# contactor_control.net
KiCad netlist of a schematic drawn in Altium Designer
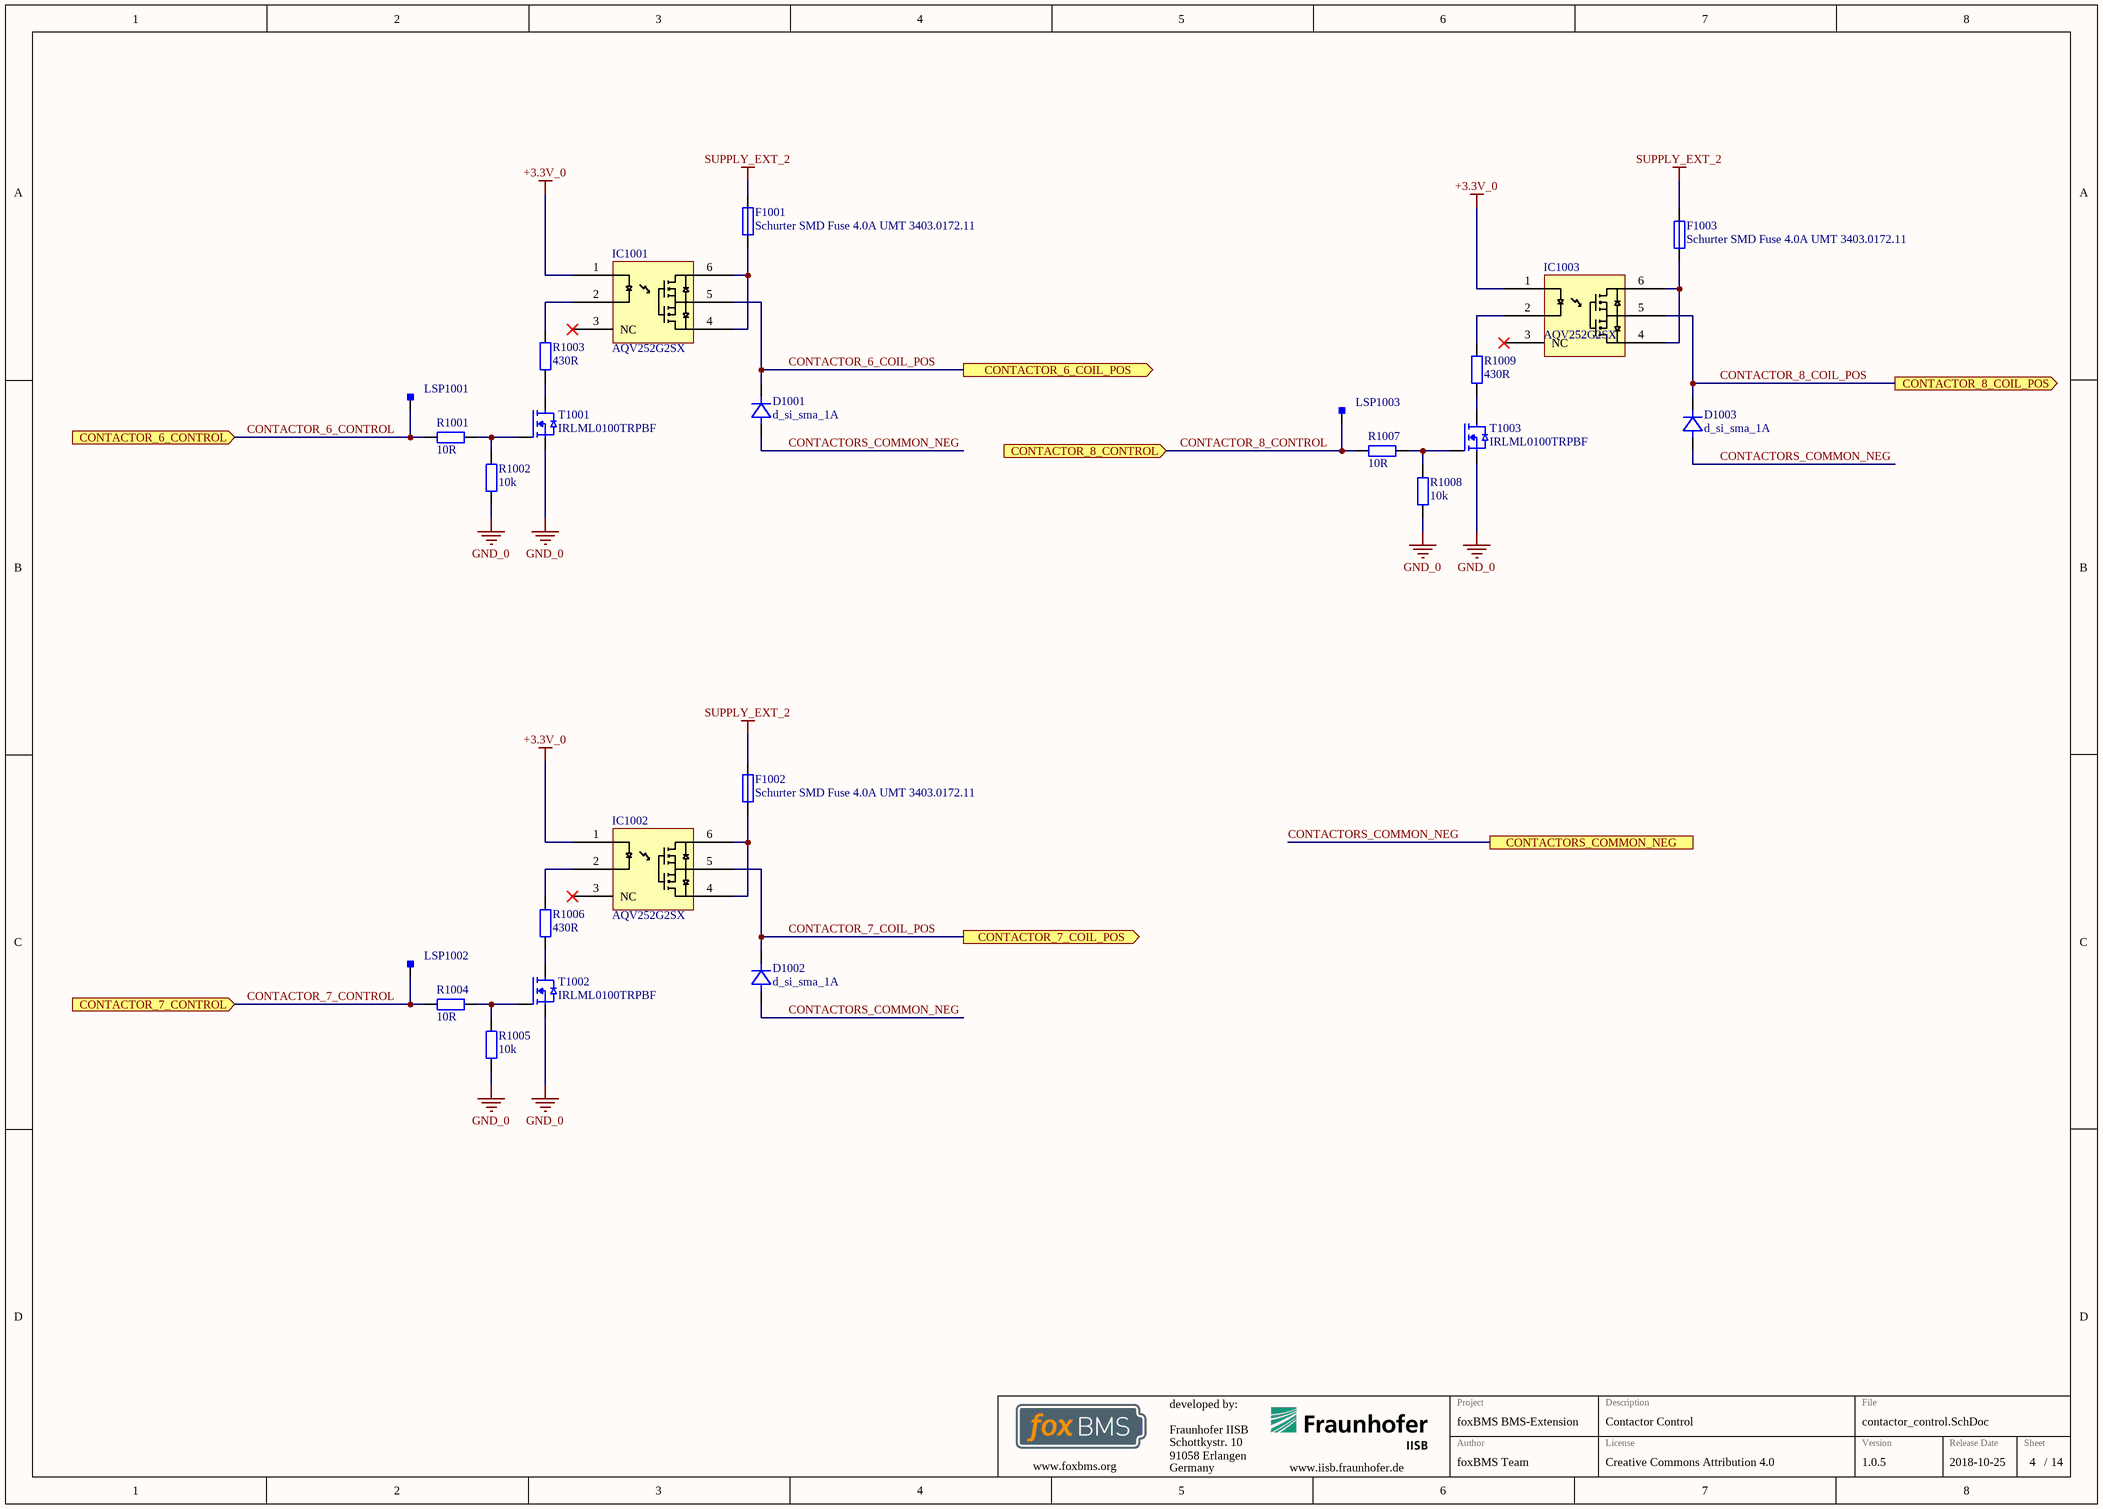
[diagram p0: contactor_control.SchDoc]

(export (version "E")
  (design (tool "Eeschema 10.0.6"))
  (components
    (comp (ref "D1001")
      (value "d_si_sma_1A")
      (footprint "DIOM4326X24N")
      (description "Standard Recovery Diode, 100 V, 1 A, Single, 1 V, 2 µs, 30 A")
      (fields (field (name "MANUFACTURER") "ON Semiconductor"))
      (libsource (lib "OE750") (part "D"))
    )
    (comp (ref "D1002")
      (value "d_si_sma_1A")
      (footprint "DIOM4326X24N")
      (description "Standard Recovery Diode, 100 V, 1 A, Single, 1 V, 2 µs, 30 A")
      (fields (field (name "MANUFACTURER") "ON Semiconductor"))
      (libsource (lib "OE750") (part "D"))
    )
    (comp (ref "D1003")
      (value "d_si_sma_1A")
      (footprint "DIOM4326X24N")
      (description "Standard Recovery Diode, 100 V, 1 A, Single, 1 V, 2 µs, 30 A")
      (fields (field (name "MANUFACTURER") "ON Semiconductor"))
      (libsource (lib "OE750") (part "D"))
    )
    (comp (ref "F1001")
      (value "Schurter SMD Fuse 4.0A UMT 3403.0172.11")
      (footprint "Schurter_UMT_250")
      (fields (field (name "PART NUMBER") "fuse_4A_3403.0172.11") (field (name "MANUFACTURER") "Schurter"))
      (libsource (lib "OE750") (part "R_Fuse"))
    )
    (comp (ref "F1002")
      (value "Schurter SMD Fuse 4.0A UMT 3403.0172.11")
      (footprint "Schurter_UMT_250")
      (fields (field (name "PART NUMBER") "fuse_4A_3403.0172.11") (field (name "MANUFACTURER") "Schurter"))
      (libsource (lib "OE750") (part "R_Fuse"))
    )
    (comp (ref "F1003")
      (value "Schurter SMD Fuse 4.0A UMT 3403.0172.11")
      (footprint "Schurter_UMT_250")
      (fields (field (name "PART NUMBER") "fuse_4A_3403.0172.11") (field (name "MANUFACTURER") "Schurter"))
      (libsource (lib "OE750") (part "R_Fuse"))
    )
    (comp (ref "IC1001")
      (value "AQV252G2SX")
      (footprint "SOP254P680X220-6N")
      (description "PhotoMOS Relay")
      (fields (field (name "MANUFACTURER") "Panasonic"))
      (libsource (lib "OE750") (part "AQV252G2SX"))
    )
    (comp (ref "IC1002")
      (value "AQV252G2SX")
      (footprint "SOP254P680X220-6N")
      (description "PhotoMOS Relay")
      (fields (field (name "MANUFACTURER") "Panasonic"))
      (libsource (lib "OE750") (part "AQV252G2SX"))
    )
    (comp (ref "IC1003")
      (value "AQV252G2SX")
      (footprint "SOP254P680X220-6N")
      (description "PhotoMOS Relay")
      (fields (field (name "MANUFACTURER") "Panasonic"))
      (libsource (lib "OE750") (part "AQV252G2SX"))
    )
    (comp (ref "LSP1001")
      (value "Testpoint_Square")
      (footprint "Testpoint_S1")
      (description "Testpoint, square")
      (libsource (lib "OE750") (part "Testpoint_Square"))
    )
    (comp (ref "LSP1002")
      (value "Testpoint_Square")
      (footprint "Testpoint_S1")
      (description "Testpoint, square")
      (libsource (lib "OE750") (part "Testpoint_Square"))
    )
    (comp (ref "LSP1003")
      (value "Testpoint_Square")
      (footprint "Testpoint_S1")
      (description "Testpoint, square")
      (libsource (lib "OE750") (part "Testpoint_Square"))
    )
    (comp (ref "R1001")
      (value "10R")
      (footprint "RESC1608X05N")
      (description "SMD Resistor 10R 0603")
      (fields (field (name "PART NUMBER") "gen_R_10R_0603") (field (name "TOLERANCE") "1%"))
      (libsource (lib "OE750") (part "R"))
    )
    (comp (ref "R1002")
      (value "10k")
      (footprint "RESC1608X05N")
      (description "SMD Resistor 10k 0603")
      (fields (field (name "PART NUMBER") "gen_R_10k_0603") (field (name "TOLERANCE") "1%"))
      (libsource (lib "OE750") (part "R"))
    )
    (comp (ref "R1003")
      (value "430R")
      (footprint "RESC1608X05N")
      (description "SMD Resistor 430R 0603")
      (fields (field (name "PART NUMBER") "gen_R_430R_0603") (field (name "TOLERANCE") "1%"))
      (libsource (lib "OE750") (part "R"))
    )
    (comp (ref "R1004")
      (value "10R")
      (footprint "RESC1608X05N")
      (description "SMD Resistor 10R 0603")
      (fields (field (name "PART NUMBER") "gen_R_10R_0603") (field (name "TOLERANCE") "1%"))
      (libsource (lib "OE750") (part "R"))
    )
    (comp (ref "R1005")
      (value "10k")
      (footprint "RESC1608X05N")
      (description "SMD Resistor 10k 0603")
      (fields (field (name "PART NUMBER") "gen_R_10k_0603") (field (name "TOLERANCE") "1%"))
      (libsource (lib "OE750") (part "R"))
    )
    (comp (ref "R1006")
      (value "430R")
      (footprint "RESC1608X05N")
      (description "SMD Resistor 430R 0603")
      (fields (field (name "PART NUMBER") "gen_R_430R_0603") (field (name "TOLERANCE") "1%"))
      (libsource (lib "OE750") (part "R"))
    )
    (comp (ref "R1007")
      (value "10R")
      (footprint "RESC1608X05N")
      (description "SMD Resistor 10R 0603")
      (fields (field (name "PART NUMBER") "gen_R_10R_0603") (field (name "TOLERANCE") "1%"))
      (libsource (lib "OE750") (part "R"))
    )
    (comp (ref "R1008")
      (value "10k")
      (footprint "RESC1608X05N")
      (description "SMD Resistor 10k 0603")
      (fields (field (name "PART NUMBER") "gen_R_10k_0603") (field (name "POWER") "0.1W"))
      (libsource (lib "OE750") (part "R"))
    )
    (comp (ref "R1009")
      (value "430R")
      (footprint "RESC1608X05N")
      (description "SMD Resistor 430R 0603")
      (fields (field (name "PART NUMBER") "gen_R_430R_0603") (field (name "TOLERANCE") "1%"))
      (libsource (lib "OE750") (part "R"))
    )
    (comp (ref "T1001")
      (value "IRLML0100TRPBF")
      (footprint "SOT95P237X110-3N")
      (description "MOSFET-Transistor, n-Kanal, 1.6 A, 100 V, 0.178 ohm, 10 V, 2.5 V")
      (fields (field (name "MANUFACTURER") "Infineon"))
      (libsource (lib "OE750") (part "NMOS"))
    )
    (comp (ref "T1002")
      (value "IRLML0100TRPBF")
      (footprint "SOT95P237X110-3N")
      (description "MOSFET-Transistor, n-Kanal, 1.6 A, 100 V, 0.178 ohm, 10 V, 2.5 V")
      (fields (field (name "MANUFACTURER") "Infineon"))
      (libsource (lib "OE750") (part "NMOS"))
    )
    (comp (ref "T1003")
      (value "IRLML0100TRPBF")
      (footprint "SOT95P237X110-3N")
      (description "MOSFET-Transistor, n-Kanal, 1.6 A, 100 V, 0.178 ohm, 10 V, 2.5 V")
      (fields (field (name "MANUFACTURER") "Infineon"))
      (libsource (lib "OE750") (part "NMOS"))
    )
  )
  (nets
    (net (code "1") (name "+3.3V_0") (class "Default")
      (node (ref "IC1001") (pin "1") (pintype "passive"))
      (node (ref "IC1002") (pin "1") (pintype "passive"))
      (node (ref "IC1003") (pin "1") (pintype "passive"))
    )
    (net (code "2") (name "/CONTACTORS_COMMON_NEG") (class "Default")
      (node (ref "D1001") (pin "2") (pinfunction "A_2") (pintype "passive"))
      (node (ref "D1002") (pin "2") (pinfunction "A_2") (pintype "passive"))
      (node (ref "D1003") (pin "2") (pinfunction "A_2") (pintype "passive"))
    )
    (net (code "3") (name "/CONTACTOR_6_COIL_POS") (class "Default")
      (node (ref "D1001") (pin "1") (pinfunction "K_1") (pintype "passive"))
      (node (ref "IC1001") (pin "5") (pintype "passive"))
    )
    (net (code "4") (name "/CONTACTOR_6_CONTROL") (class "Default")
      (node (ref "LSP1001") (pin "1") (pinfunction "1_1") (pintype "passive"))
      (node (ref "R1001") (pin "2") (pinfunction "2_2") (pintype "passive"))
    )
    (net (code "5") (name "/CONTACTOR_7_COIL_POS") (class "Default")
      (node (ref "D1002") (pin "1") (pinfunction "K_1") (pintype "passive"))
      (node (ref "IC1002") (pin "5") (pintype "passive"))
    )
    (net (code "6") (name "/CONTACTOR_7_CONTROL") (class "Default")
      (node (ref "LSP1002") (pin "1") (pinfunction "1_1") (pintype "passive"))
      (node (ref "R1004") (pin "2") (pinfunction "2_2") (pintype "passive"))
    )
    (net (code "7") (name "/CONTACTOR_8_COIL_POS") (class "Default")
      (node (ref "D1003") (pin "1") (pinfunction "K_1") (pintype "passive"))
      (node (ref "IC1003") (pin "5") (pintype "passive"))
    )
    (net (code "8") (name "/CONTACTOR_8_CONTROL") (class "Default")
      (node (ref "LSP1003") (pin "1") (pinfunction "1_1") (pintype "passive"))
      (node (ref "R1007") (pin "2") (pinfunction "2_2") (pintype "passive"))
    )
    (net (code "9") (name "GND_0") (class "Default")
      (node (ref "R1002") (pin "1") (pinfunction "1_1") (pintype "passive"))
      (node (ref "R1005") (pin "1") (pinfunction "1_1") (pintype "passive"))
      (node (ref "R1008") (pin "1") (pinfunction "1_1") (pintype "passive"))
      (node (ref "T1001") (pin "S") (pinfunction "S_S") (pintype "passive"))
      (node (ref "T1002") (pin "S") (pinfunction "S_S") (pintype "passive"))
      (node (ref "T1003") (pin "S") (pinfunction "S_S") (pintype "passive"))
    )
    (net (code "10") (name "Net-(F1001-Pad1)") (class "Default")
      (node (ref "F1001") (pin "1") (pinfunction "1_1") (pintype "passive"))
      (node (ref "IC1001") (pin "4") (pintype "passive"))
      (node (ref "IC1001") (pin "6") (pintype "passive"))
    )
    (net (code "11") (name "Net-(F1002-Pad1)") (class "Default")
      (node (ref "F1002") (pin "1") (pinfunction "1_1") (pintype "passive"))
      (node (ref "IC1002") (pin "4") (pintype "passive"))
      (node (ref "IC1002") (pin "6") (pintype "passive"))
    )
    (net (code "12") (name "Net-(F1003-Pad1)") (class "Default")
      (node (ref "F1003") (pin "1") (pinfunction "1_1") (pintype "passive"))
      (node (ref "IC1003") (pin "4") (pintype "passive"))
      (node (ref "IC1003") (pin "6") (pintype "passive"))
    )
    (net (code "13") (name "Net-(IC1001-Pad2)") (class "Default")
      (node (ref "IC1001") (pin "2") (pintype "power_in"))
      (node (ref "R1003") (pin "2") (pinfunction "2_2") (pintype "passive"))
    )
    (net (code "14") (name "Net-(IC1002-Pad2)") (class "Default")
      (node (ref "IC1002") (pin "2") (pintype "power_in"))
      (node (ref "R1006") (pin "2") (pinfunction "2_2") (pintype "passive"))
    )
    (net (code "15") (name "Net-(IC1003-Pad2)") (class "Default")
      (node (ref "IC1003") (pin "2") (pintype "power_in"))
      (node (ref "R1009") (pin "2") (pinfunction "2_2") (pintype "passive"))
    )
    (net (code "16") (name "Net-(R1001-Pad1)") (class "Default")
      (node (ref "R1001") (pin "1") (pinfunction "1_1") (pintype "passive"))
      (node (ref "R1002") (pin "2") (pinfunction "2_2") (pintype "passive"))
      (node (ref "T1001") (pin "G") (pinfunction "G_G") (pintype "passive"))
    )
    (net (code "17") (name "Net-(R1003-Pad1)") (class "Default")
      (node (ref "R1003") (pin "1") (pinfunction "1_1") (pintype "passive"))
      (node (ref "T1001") (pin "D") (pinfunction "D_D") (pintype "passive"))
    )
    (net (code "18") (name "Net-(R1004-Pad1)") (class "Default")
      (node (ref "R1004") (pin "1") (pinfunction "1_1") (pintype "passive"))
      (node (ref "R1005") (pin "2") (pinfunction "2_2") (pintype "passive"))
      (node (ref "T1002") (pin "G") (pinfunction "G_G") (pintype "passive"))
    )
    (net (code "19") (name "Net-(R1006-Pad1)") (class "Default")
      (node (ref "R1006") (pin "1") (pinfunction "1_1") (pintype "passive"))
      (node (ref "T1002") (pin "D") (pinfunction "D_D") (pintype "passive"))
    )
    (net (code "20") (name "Net-(R1007-Pad1)") (class "Default")
      (node (ref "R1007") (pin "1") (pinfunction "1_1") (pintype "passive"))
      (node (ref "R1008") (pin "2") (pinfunction "2_2") (pintype "passive"))
      (node (ref "T1003") (pin "G") (pinfunction "G_G") (pintype "passive"))
    )
    (net (code "21") (name "Net-(R1009-Pad1)") (class "Default")
      (node (ref "R1009") (pin "1") (pinfunction "1_1") (pintype "passive"))
      (node (ref "T1003") (pin "D") (pinfunction "D_D") (pintype "passive"))
    )
    (net (code "22") (name "SUPPLY_EXT_2") (class "Default")
      (node (ref "F1001") (pin "2") (pinfunction "2_2") (pintype "passive"))
      (node (ref "F1002") (pin "2") (pinfunction "2_2") (pintype "passive"))
      (node (ref "F1003") (pin "2") (pinfunction "2_2") (pintype "passive"))
    )
    (net (code "23") (name "unconnected-(IC1001-NC-Pad3)") (class "Default")
      (node (ref "IC1001") (pin "3") (pinfunction "NC_3") (pintype "passive+no_connect"))
    )
    (net (code "24") (name "unconnected-(IC1002-NC-Pad3)") (class "Default")
      (node (ref "IC1002") (pin "3") (pinfunction "NC_3") (pintype "passive+no_connect"))
    )
    (net (code "25") (name "unconnected-(IC1003-NC-Pad3)") (class "Default")
      (node (ref "IC1003") (pin "3") (pinfunction "NC_3") (pintype "passive+no_connect"))
    )
  )
)
